# Sensor_Board_0x04_Luminosity_TSL2561_v1.net
KiCad netlist of a schematic drawn in EAGLE
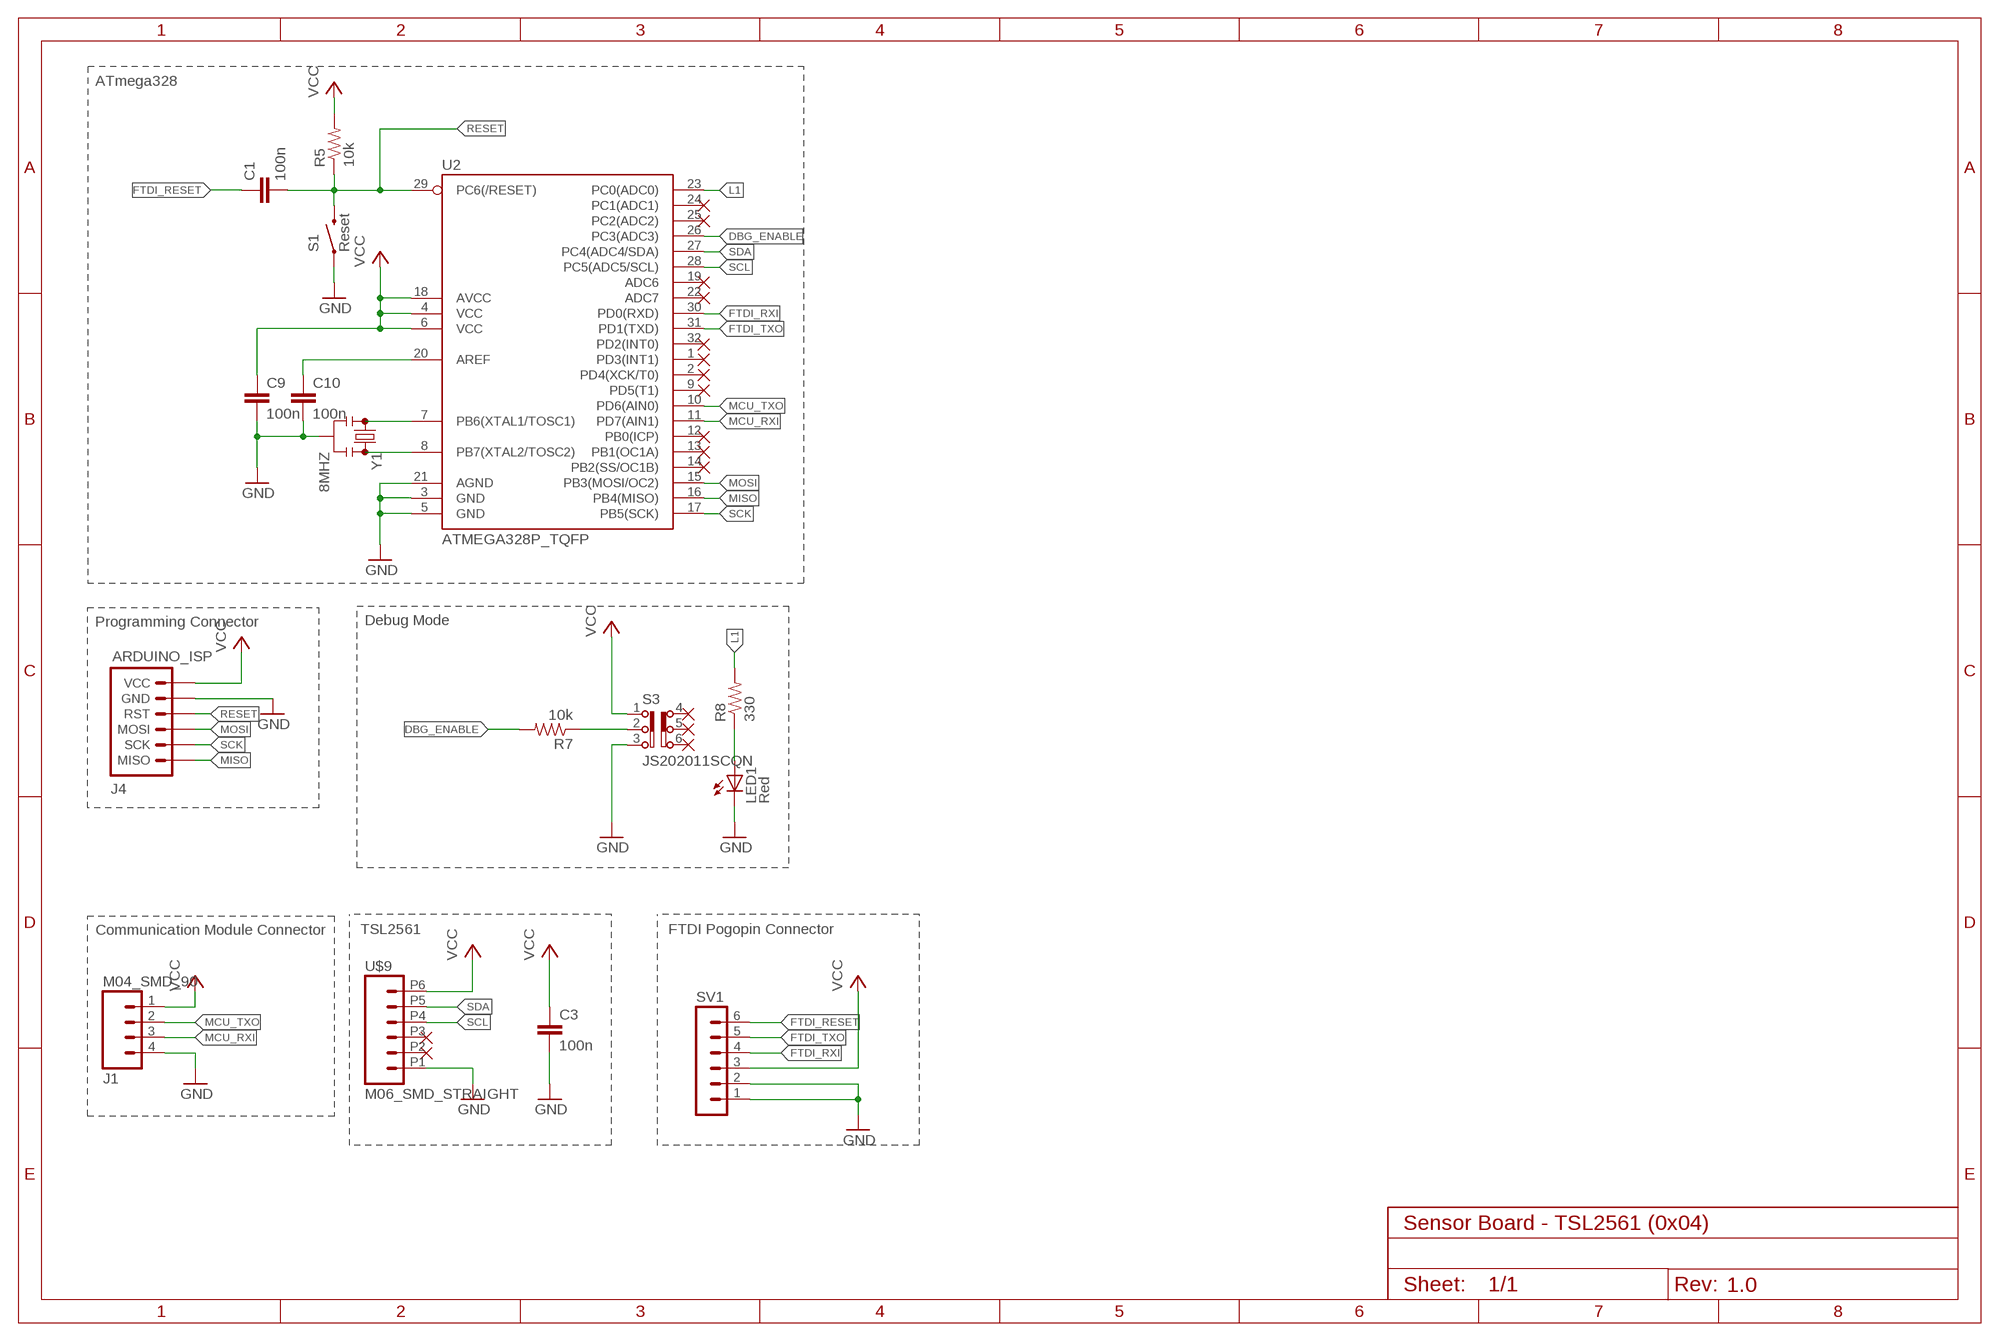
[diagram p0: schematic, sheet 1]

(export (version "E")
  (design (tool "Eeschema 10.0.6"))
  (components
    (comp (ref "C1")
      (value "100n")
      (footprint "eagle-import:C0805")
      (libsource (lib "eagle-import") (part "C"))
    )
    (comp (ref "C3")
      (value "100n")
      (footprint "eagle-import:C0805")
      (libsource (lib "eagle-import") (part "C"))
    )
    (comp (ref "C9")
      (value "100n")
      (footprint "eagle-import:C0805")
      (libsource (lib "eagle-import") (part "C"))
    )
    (comp (ref "C10")
      (value "100n")
      (footprint "eagle-import:C0805")
      (libsource (lib "eagle-import") (part "C"))
    )
    (comp (ref "J1")
      (value "M04_SMD_90")
      (footprint "eagle-import:M04_SMD_90")
      (libsource (lib "eagle-import") (part "M04_SMD_90"))
    )
    (comp (ref "J4")
      (value "ARDUINO_ISP")
      (footprint "eagle-import:M-2X3")
      (libsource (lib "eagle-import") (part "ARDUINO_ISP"))
    )
    (comp (ref "LED1")
      (value "Red")
      (footprint "eagle-import:SML0805")
      (libsource (lib "eagle-import") (part "LEDSML0805"))
    )
    (comp (ref "R5")
      (value "10k")
      (footprint "eagle-import:0805")
      (libsource (lib "eagle-import") (part "RESISTOR0805-RES"))
    )
    (comp (ref "R7")
      (value "10k")
      (footprint "eagle-import:0805")
      (libsource (lib "eagle-import") (part "RESISTOR0805-RES"))
    )
    (comp (ref "R8")
      (value "330")
      (footprint "eagle-import:0805")
      (libsource (lib "eagle-import") (part "RESISTOR0805-RES"))
    )
    (comp (ref "S1")
      (value "Reset")
      (footprint "eagle-import:M-PUSHBUTTON-SMD")
      (libsource (lib "eagle-import") (part "PUSHBUTTON"))
    )
    (comp (ref "S3")
      (value "JS202011SCQN")
      (footprint "eagle-import:JS202011SCQN")
      (libsource (lib "eagle-import") (part "JS202011SCQN"))
    )
    (comp (ref "SV1")
      (value "MA06-1")
      (footprint "eagle-import:MA06-1")
      (libsource (lib "eagle-import") (part "MA06-1"))
    )
    (comp (ref "U$9")
      (value "M06_SMD_STRAIGHT")
      (footprint "eagle-import:M06_SMD_STRAIGHT")
      (libsource (lib "eagle-import") (part "M06_SMD_STRAIGHT"))
    )
    (comp (ref "U2")
      (value "ATMEGA328P_TQFP")
      (footprint "eagle-import:TQFP32-08")
      (libsource (lib "eagle-import") (part "ATMEGA328P_TQFP"))
    )
    (comp (ref "Y1")
      (value "8MHZ")
      (footprint "eagle-import:RESONATOR-SMD")
      (libsource (lib "eagle-import") (part "RESONATOR8MHZ"))
    )
  )
  (nets
    (net (code "1") (name "DBG_ENABLE") (class "Default")
      (node (ref "R7") (pin "2") (pinfunction "2_2") (pintype "passive"))
      (node (ref "U2") (pin "26") (pinfunction "PC3(ADC3)_26") (pintype "bidirectional"))
    )
    (net (code "2") (name "FTDI_RESET") (class "Default")
      (node (ref "C1") (pin "1") (pinfunction "1_1") (pintype "passive"))
      (node (ref "SV1") (pin "6") (pinfunction "6_6") (pintype "passive"))
    )
    (net (code "3") (name "FTDI_RXI") (class "Default")
      (node (ref "SV1") (pin "4") (pinfunction "4_4") (pintype "passive"))
      (node (ref "U2") (pin "30") (pinfunction "PD0(RXD)_30") (pintype "bidirectional"))
    )
    (net (code "4") (name "FTDI_TXO") (class "Default")
      (node (ref "SV1") (pin "5") (pinfunction "5_5") (pintype "passive"))
      (node (ref "U2") (pin "31") (pinfunction "PD1(TXD)_31") (pintype "bidirectional"))
    )
    (net (code "5") (name "GND") (class "Default")
      (node (ref "C10") (pin "2") (pinfunction "2_2") (pintype "passive"))
      (node (ref "C3") (pin "2") (pinfunction "2_2") (pintype "passive"))
      (node (ref "C9") (pin "2") (pinfunction "2_2") (pintype "passive"))
      (node (ref "J1") (pin "4") (pinfunction "4_4") (pintype "passive"))
      (node (ref "J4") (pin "P$5") (pinfunction "GND_P$5") (pintype "passive"))
      (node (ref "LED1") (pin "C") (pinfunction "C_C") (pintype "passive"))
      (node (ref "S1") (pin "1") (pinfunction "LEFT_1") (pintype "passive"))
      (node (ref "S1") (pin "2") (pinfunction "LEFT_2") (pintype "passive"))
      (node (ref "S3") (pin "3") (pinfunction "3_3") (pintype "passive"))
      (node (ref "SV1") (pin "1") (pinfunction "1_1") (pintype "passive"))
      (node (ref "SV1") (pin "2") (pinfunction "2_2") (pintype "passive"))
      (node (ref "U$9") (pin "P1") (pinfunction "1_P1") (pintype "passive"))
      (node (ref "U2") (pin "21") (pinfunction "AGND_21") (pintype "bidirectional"))
      (node (ref "U2") (pin "3") (pinfunction "GND_3") (pintype "bidirectional"))
      (node (ref "U2") (pin "5") (pinfunction "GND_5") (pintype "bidirectional"))
      (node (ref "Y1") (pin "2") (pinfunction "2_2") (pintype "passive"))
    )
    (net (code "6") (name "L1") (class "Default")
      (node (ref "R8") (pin "2") (pinfunction "2_2") (pintype "passive"))
      (node (ref "U2") (pin "23") (pinfunction "PC0(ADC0)_23") (pintype "bidirectional"))
    )
    (net (code "7") (name "MCU_RXI") (class "Default")
      (node (ref "J1") (pin "3") (pinfunction "3_3") (pintype "passive"))
      (node (ref "U2") (pin "11") (pinfunction "PD7(AIN1)_11") (pintype "bidirectional"))
    )
    (net (code "8") (name "MCU_TXO") (class "Default")
      (node (ref "J1") (pin "2") (pinfunction "2_2") (pintype "passive"))
      (node (ref "U2") (pin "10") (pinfunction "PD6(AIN0)_10") (pintype "bidirectional"))
    )
    (net (code "9") (name "MISO") (class "Default")
      (node (ref "J4") (pin "P$1") (pinfunction "MISO_P$1") (pintype "passive"))
      (node (ref "U2") (pin "16") (pinfunction "PB4(MISO)_16") (pintype "bidirectional"))
    )
    (net (code "10") (name "MOSI") (class "Default")
      (node (ref "J4") (pin "P$3") (pinfunction "MOSI_P$3") (pintype "passive"))
      (node (ref "U2") (pin "15") (pinfunction "PB3(MOSI/OC2)_15") (pintype "bidirectional"))
    )
    (net (code "11") (name "Net-(LED1-PadA)") (class "Default")
      (node (ref "LED1") (pin "A") (pinfunction "A_A") (pintype "passive"))
      (node (ref "R8") (pin "1") (pinfunction "1_1") (pintype "passive"))
    )
    (net (code "12") (name "Net-(R7-Pad1)") (class "Default")
      (node (ref "R7") (pin "1") (pinfunction "1_1") (pintype "passive"))
      (node (ref "S3") (pin "2") (pinfunction "2_2") (pintype "passive"))
    )
    (net (code "13") (name "Net-(U2-AREF)") (class "Default")
      (node (ref "C10") (pin "1") (pinfunction "1_1") (pintype "passive"))
      (node (ref "U2") (pin "20") (pinfunction "AREF_20") (pintype "bidirectional"))
    )
    (net (code "14") (name "Net-(U2-PB6(XTAL1{slash}TOSC1))") (class "Default")
      (node (ref "U2") (pin "7") (pinfunction "PB6(XTAL1/TOSC1)_7") (pintype "bidirectional"))
      (node (ref "Y1") (pin "1") (pinfunction "1_1") (pintype "passive"))
    )
    (net (code "15") (name "Net-(U2-PB7(XTAL2{slash}TOSC2))") (class "Default")
      (node (ref "U2") (pin "8") (pinfunction "PB7(XTAL2/TOSC2)_8") (pintype "bidirectional"))
      (node (ref "Y1") (pin "3") (pinfunction "3_3") (pintype "passive"))
    )
    (net (code "16") (name "RESET") (class "Default")
      (node (ref "C1") (pin "2") (pinfunction "2_2") (pintype "passive"))
      (node (ref "J4") (pin "P$4") (pinfunction "RST_P$4") (pintype "passive"))
      (node (ref "R5") (pin "1") (pinfunction "1_1") (pintype "passive"))
      (node (ref "S1") (pin "3") (pinfunction "RIGHT_3") (pintype "passive"))
      (node (ref "S1") (pin "4") (pinfunction "RIGHT_4") (pintype "passive"))
      (node (ref "U2") (pin "29") (pinfunction "PC6(/RESET)_29") (pintype "bidirectional"))
    )
    (net (code "17") (name "SCK") (class "Default")
      (node (ref "J4") (pin "P$2") (pinfunction "SCK_P$2") (pintype "passive"))
      (node (ref "U2") (pin "17") (pinfunction "PB5(SCK)_17") (pintype "bidirectional"))
    )
    (net (code "18") (name "SCL") (class "Default")
      (node (ref "U$9") (pin "P4") (pinfunction "4_P4") (pintype "passive"))
      (node (ref "U2") (pin "28") (pinfunction "PC5(ADC5/SCL)_28") (pintype "bidirectional"))
    )
    (net (code "19") (name "SDA") (class "Default")
      (node (ref "U$9") (pin "P5") (pinfunction "5_P5") (pintype "passive"))
      (node (ref "U2") (pin "27") (pinfunction "PC4(ADC4/SDA)_27") (pintype "bidirectional"))
    )
    (net (code "20") (name "VCC") (class "Default")
      (node (ref "C3") (pin "1") (pinfunction "1_1") (pintype "passive"))
      (node (ref "C9") (pin "1") (pinfunction "1_1") (pintype "passive"))
      (node (ref "J1") (pin "1") (pinfunction "1_1") (pintype "passive"))
      (node (ref "J4") (pin "P$6") (pinfunction "VCC_P$6") (pintype "passive"))
      (node (ref "R5") (pin "2") (pinfunction "2_2") (pintype "passive"))
      (node (ref "S3") (pin "1") (pinfunction "1_1") (pintype "passive"))
      (node (ref "SV1") (pin "3") (pinfunction "3_3") (pintype "passive"))
      (node (ref "U$9") (pin "P6") (pinfunction "6_P6") (pintype "passive"))
      (node (ref "U2") (pin "18") (pinfunction "AVCC_18") (pintype "bidirectional"))
      (node (ref "U2") (pin "4") (pinfunction "VCC_4") (pintype "bidirectional"))
      (node (ref "U2") (pin "6") (pinfunction "VCC_6") (pintype "bidirectional"))
    )
    (net (code "21") (name "unconnected-(S3-Pad4)") (class "Default")
      (node (ref "S3") (pin "4") (pinfunction "4_4") (pintype "passive"))
    )
    (net (code "22") (name "unconnected-(S3-Pad5)") (class "Default")
      (node (ref "S3") (pin "5") (pinfunction "5_5") (pintype "passive"))
    )
    (net (code "23") (name "unconnected-(S3-Pad6)") (class "Default")
      (node (ref "S3") (pin "6") (pinfunction "6_6") (pintype "passive"))
    )
    (net (code "24") (name "unconnected-(U$9-2-PadP2)") (class "Default")
      (node (ref "U$9") (pin "P2") (pinfunction "2_P2") (pintype "passive"))
    )
    (net (code "25") (name "unconnected-(U$9-3-PadP3)") (class "Default")
      (node (ref "U$9") (pin "P3") (pinfunction "3_P3") (pintype "passive"))
    )
    (net (code "26") (name "unconnected-(U2-ADC6-Pad19)") (class "Default")
      (node (ref "U2") (pin "19") (pinfunction "ADC6_19") (pintype "bidirectional"))
    )
    (net (code "27") (name "unconnected-(U2-ADC7-Pad22)") (class "Default")
      (node (ref "U2") (pin "22") (pinfunction "ADC7_22") (pintype "bidirectional"))
    )
    (net (code "28") (name "unconnected-(U2-PB0(ICP)-Pad12)") (class "Default")
      (node (ref "U2") (pin "12") (pinfunction "PB0(ICP)_12") (pintype "bidirectional"))
    )
    (net (code "29") (name "unconnected-(U2-PB1(OC1A)-Pad13)") (class "Default")
      (node (ref "U2") (pin "13") (pinfunction "PB1(OC1A)_13") (pintype "bidirectional"))
    )
    (net (code "30") (name "unconnected-(U2-PB2(SS{slash}OC1B)-Pad14)") (class "Default")
      (node (ref "U2") (pin "14") (pinfunction "PB2(SS/OC1B)_14") (pintype "bidirectional"))
    )
    (net (code "31") (name "unconnected-(U2-PC1(ADC1)-Pad24)") (class "Default")
      (node (ref "U2") (pin "24") (pinfunction "PC1(ADC1)_24") (pintype "bidirectional"))
    )
    (net (code "32") (name "unconnected-(U2-PC2(ADC2)-Pad25)") (class "Default")
      (node (ref "U2") (pin "25") (pinfunction "PC2(ADC2)_25") (pintype "bidirectional"))
    )
    (net (code "33") (name "unconnected-(U2-PD2(INT0)-Pad32)") (class "Default")
      (node (ref "U2") (pin "32") (pinfunction "PD2(INT0)_32") (pintype "bidirectional"))
    )
    (net (code "34") (name "unconnected-(U2-PD3(INT1)-Pad1)") (class "Default")
      (node (ref "U2") (pin "1") (pinfunction "PD3(INT1)_1") (pintype "bidirectional"))
    )
    (net (code "35") (name "unconnected-(U2-PD4(XCK{slash}T0)-Pad2)") (class "Default")
      (node (ref "U2") (pin "2") (pinfunction "PD4(XCK/T0)_2") (pintype "bidirectional"))
    )
    (net (code "36") (name "unconnected-(U2-PD5(T1)-Pad9)") (class "Default")
      (node (ref "U2") (pin "9") (pinfunction "PD5(T1)_9") (pintype "bidirectional"))
    )
  )
)
